# MAGIsCM4Core.net
KiCad netlist of a schematic drawn in Altium Designer
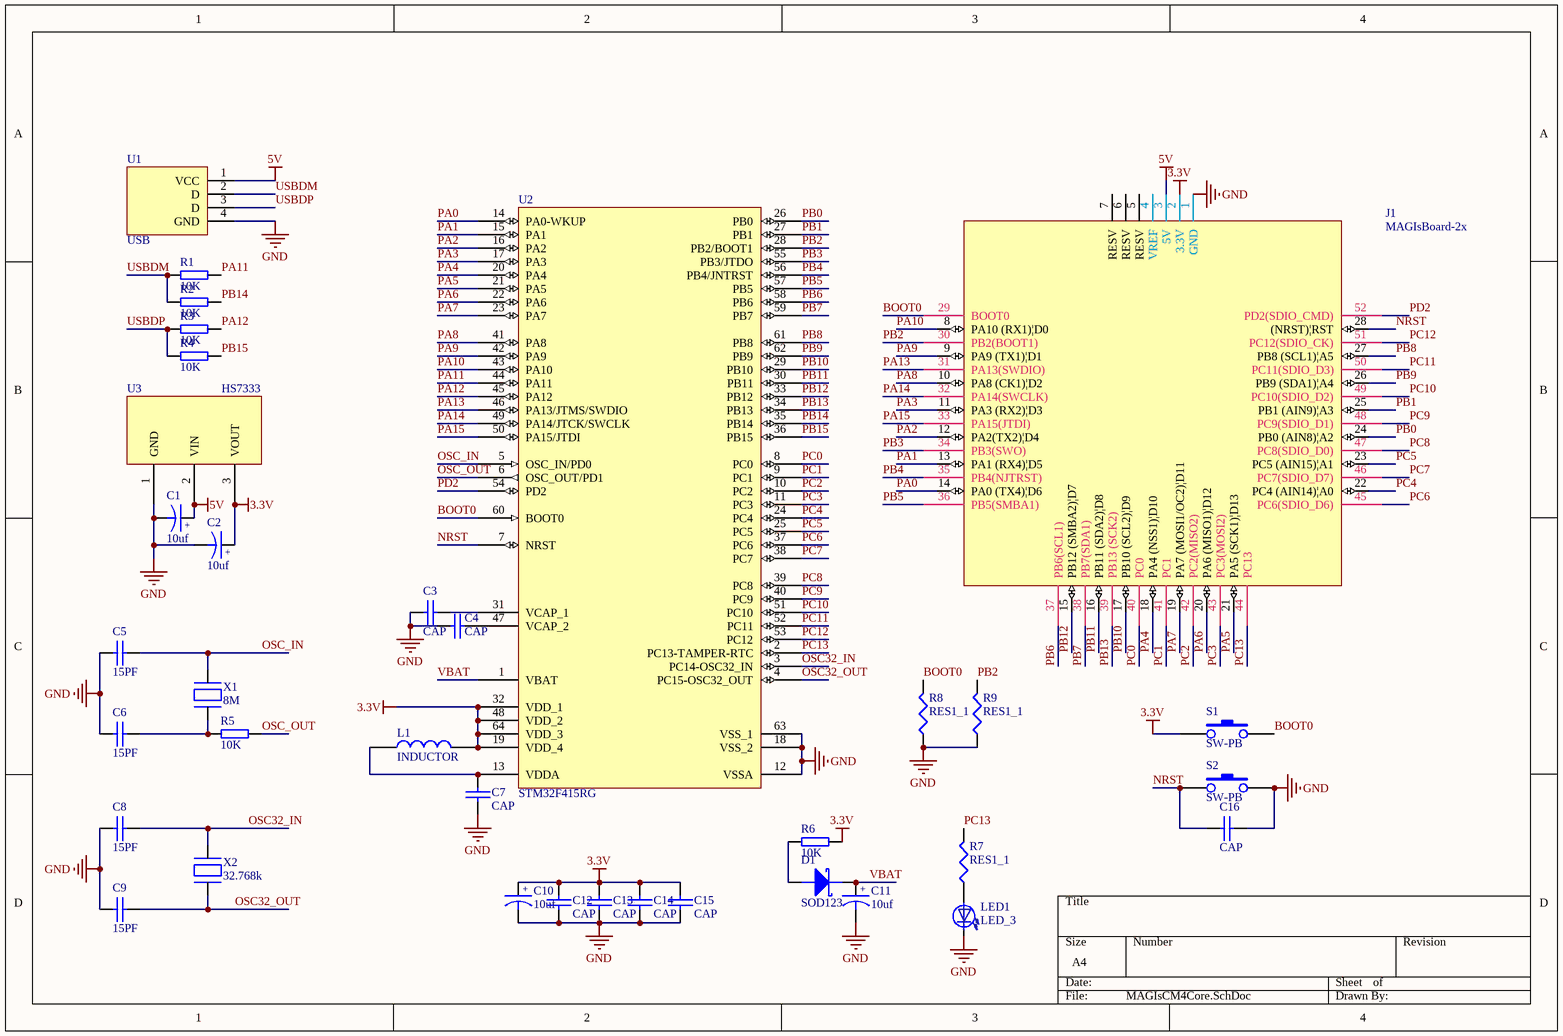
[diagram p0: MAGIsCM4Core.SchDoc]

(export (version "E")
  (design (tool "Eeschema 10.0.6"))
  (components
    (comp (ref "C1")
      (value "10uf")
      (footprint "6-0805_n")
      (description "Capacitor")
      (libsource (lib "电容器") (part "CAPACITOR POL"))
    )
    (comp (ref "C2")
      (value "10uf")
      (footprint "6-0805_n")
      (description "Capacitor")
      (libsource (lib "电容器") (part "CAPACITOR POL"))
    )
    (comp (ref "C3")
      (value "CAP")
      (footprint "6-0805_N")
      (description "Capacitor")
      (libsource (lib "电容器") (part "CAP_1"))
    )
    (comp (ref "C4")
      (value "CAP")
      (footprint "6-0805_N")
      (description "Capacitor")
      (libsource (lib "电容器") (part "CAP_1"))
    )
    (comp (ref "C5") (value "15PF") (footprint "6-0805_n") (libsource (lib "STM32") (part "CAP")))
    (comp (ref "C6") (value "15PF") (footprint "6-0805_n") (libsource (lib "STM32") (part "CAP")))
    (comp (ref "C7")
      (value "CAP")
      (footprint "6-0805_N")
      (description "Capacitor")
      (libsource (lib "电容器") (part "CAP_1"))
    )
    (comp (ref "C8") (value "15PF") (footprint "1608[0603]") (libsource (lib "STM32") (part "CAP")))
    (comp (ref "C9") (value "15PF") (footprint "1608[0603]") (libsource (lib "STM32") (part "CAP")))
    (comp (ref "C10")
      (value "10uf")
      (footprint "C1210_N")
      (description "Capacitor")
      (libsource (lib "电容器") (part "CAPACITOR POL"))
    )
    (comp (ref "C11")
      (value "10uf")
      (footprint "3.3V0.2F-RK")
      (description "Capacitor")
      (libsource (lib "电容器") (part "CAPACITOR POL"))
    )
    (comp (ref "C12")
      (value "CAP")
      (footprint "6-0805_N")
      (description "Capacitor")
      (libsource (lib "电容器") (part "CAP_1"))
    )
    (comp (ref "C13")
      (value "CAP")
      (footprint "6-0805_N")
      (description "Capacitor")
      (libsource (lib "电容器") (part "CAP_1"))
    )
    (comp (ref "C14")
      (value "CAP")
      (footprint "6-0805_N")
      (description "Capacitor")
      (libsource (lib "电容器") (part "CAP_1"))
    )
    (comp (ref "C15")
      (value "CAP")
      (footprint "6-0805_N")
      (description "Capacitor")
      (libsource (lib "电容器") (part "CAP_1"))
    )
    (comp (ref "C16")
      (value "CAP")
      (footprint "6-0805_N")
      (description "Capacitor")
      (libsource (lib "电容器") (part "CAP_1"))
    )
    (comp (ref "D1")
      (value "SOD123")
      (footprint "LL34")
      (description "Schottky Diode")
      (libsource (lib "二极管") (part "DIODE SCHOTTKY_1"))
    )
    (comp (ref "J1")
      (value "MAGIsBoard-2x")
      (footprint "MAGIsBoard-2x")
      (libsource (lib "MAGIsBoard") (part "MAGIsBoard-2x"))
    )
    (comp (ref "L1") (value "INDUCTOR") (footprint "6-0805_n") (libsource (lib "汇总") (part "INDUCTOR")))
    (comp (ref "LED1") (value "LED_3") (footprint "6-0805_N") (libsource (lib "二极管") (part "LED_3")))
    (comp (ref "R1") (value "10K") (footprint "6-0805_n") (libsource (lib "STM32") (part "RES")))
    (comp (ref "R2") (value "10K") (footprint "6-0805_n") (libsource (lib "STM32") (part "RES")))
    (comp (ref "R3") (value "10K") (footprint "6-0805_n") (libsource (lib "STM32") (part "RES")))
    (comp (ref "R4") (value "10K") (footprint "6-0805_n") (libsource (lib "STM32") (part "RES")))
    (comp (ref "R5") (value "10K") (footprint "6-0805_n") (libsource (lib "STM32") (part "RES")))
    (comp (ref "R6") (value "10K") (footprint "6-0805_n") (libsource (lib "STM32") (part "RES")))
    (comp (ref "R7") (value "RES1_1") (footprint "6-0805_N") (libsource (lib "电阻器") (part "RES1_1")))
    (comp (ref "R8") (value "RES1_1") (footprint "6-0805_N") (libsource (lib "电阻器") (part "RES1_1")))
    (comp (ref "R9") (value "RES1_1") (footprint "6-0805_N") (libsource (lib "电阻器") (part "RES1_1")))
    (comp (ref "S1") (value "SW-PB") (footprint "SKRELGE010") (libsource (lib "手动开关") (part "SW-PB")))
    (comp (ref "S2") (value "SW-PB") (footprint "SKRELGE010") (libsource (lib "手动开关") (part "SW-PB")))
    (comp (ref "U1") (value "USB") (footprint "microUSB") (libsource (lib "USB接口") (part "USB")))
    (comp (ref "U2")
      (value "STM32F415RG")
      (footprint "STM32F415RG")
      (libsource (lib "MCU") (part "STM32F415RG"))
    )
    (comp (ref "U3") (value "HS7333") (footprint "HS7333") (libsource (lib "PMIC") (part "HS7333")))
    (comp (ref "X1") (value "8M") (footprint "5032") (libsource (lib "STM32") (part "CRYSTAL")))
    (comp (ref "X2") (value "32.768k") (footprint "3215") (libsource (lib "STM32") (part "CRYSTAL")))
  )
  (nets
    (net (code "1") (name "/BOOT0") (class "Default")
      (node (ref "J1") (pin "29") (pinfunction "BOOT0_29") (pintype "passive"))
      (node (ref "R8") (pin "2") (pinfunction "2_2") (pintype "passive"))
      (node (ref "S1") (pin "2") (pinfunction "2_2") (pintype "passive"))
      (node (ref "U2") (pin "60") (pinfunction "BOOT0_60") (pintype "input"))
    )
    (net (code "2") (name "/NRST") (class "Default")
      (node (ref "C16") (pin "2") (pinfunction "2_2") (pintype "passive"))
      (node (ref "J1") (pin "28") (pinfunction "(NRST)¦RST_28") (pintype "bidirectional"))
      (node (ref "S2") (pin "1") (pinfunction "1_1") (pintype "passive"))
      (node (ref "U2") (pin "7") (pinfunction "NRST_7") (pintype "bidirectional"))
    )
    (net (code "3") (name "/OSC32_IN") (class "Default")
      (node (ref "C8") (pin "2") (pinfunction "2_2") (pintype "passive"))
      (node (ref "U2") (pin "3") (pinfunction "PC14-OSC32_IN_3") (pintype "bidirectional"))
      (node (ref "X2") (pin "1") (pinfunction "1_1") (pintype "passive"))
    )
    (net (code "4") (name "/OSC32_OUT") (class "Default")
      (node (ref "C9") (pin "2") (pinfunction "2_2") (pintype "passive"))
      (node (ref "U2") (pin "4") (pinfunction "PC15-OSC32_OUT_4") (pintype "bidirectional"))
      (node (ref "X2") (pin "2") (pinfunction "2_2") (pintype "passive"))
    )
    (net (code "5") (name "/OSC_IN") (class "Default")
      (node (ref "C5") (pin "2") (pinfunction "2_2") (pintype "passive"))
      (node (ref "U2") (pin "5") (pinfunction "OSC_IN/PD0_5") (pintype "input"))
      (node (ref "X1") (pin "1") (pinfunction "1_1") (pintype "passive"))
    )
    (net (code "6") (name "/OSC_OUT") (class "Default")
      (node (ref "R5") (pin "1") (pinfunction "1_1") (pintype "passive"))
      (node (ref "U2") (pin "6") (pinfunction "OSC_OUT/PD1_6") (pintype "output"))
    )
    (net (code "7") (name "/PA0") (class "Default")
      (node (ref "J1") (pin "14") (pinfunction "PA0_(TX4)¦D6_14") (pintype "bidirectional"))
      (node (ref "U2") (pin "14") (pinfunction "PA0-WKUP_14") (pintype "bidirectional"))
    )
    (net (code "8") (name "/PA1") (class "Default")
      (node (ref "J1") (pin "13") (pinfunction "PA1_(RX4)¦D5_13") (pintype "bidirectional"))
      (node (ref "U2") (pin "15") (pinfunction "PA1_15") (pintype "bidirectional"))
    )
    (net (code "9") (name "/PA2") (class "Default")
      (node (ref "J1") (pin "12") (pinfunction "PA2(TX2)¦D4_12") (pintype "bidirectional"))
      (node (ref "U2") (pin "16") (pinfunction "PA2_16") (pintype "bidirectional"))
    )
    (net (code "10") (name "/PA3") (class "Default")
      (node (ref "J1") (pin "11") (pinfunction "PA3_(RX2)¦D3_11") (pintype "bidirectional"))
      (node (ref "U2") (pin "17") (pinfunction "PA3_17") (pintype "bidirectional"))
    )
    (net (code "11") (name "/PA4") (class "Default")
      (node (ref "J1") (pin "18") (pinfunction "PA4_(NSS1)¦D10_18") (pintype "bidirectional"))
      (node (ref "U2") (pin "20") (pinfunction "PA4_20") (pintype "bidirectional"))
    )
    (net (code "12") (name "/PA5") (class "Default")
      (node (ref "J1") (pin "21") (pinfunction "PA5_(SCK1)¦D13_21") (pintype "bidirectional"))
      (node (ref "U2") (pin "21") (pinfunction "PA5_21") (pintype "bidirectional"))
    )
    (net (code "13") (name "/PA6") (class "Default")
      (node (ref "J1") (pin "20") (pinfunction "PA6_(MISO1)¦D12_20") (pintype "bidirectional"))
      (node (ref "U2") (pin "22") (pinfunction "PA6_22") (pintype "bidirectional"))
    )
    (net (code "14") (name "/PA7") (class "Default")
      (node (ref "J1") (pin "19") (pinfunction "PA7_(MOSI1/OC2)¦D11_19") (pintype "bidirectional"))
      (node (ref "U2") (pin "23") (pinfunction "PA7_23") (pintype "bidirectional"))
    )
    (net (code "15") (name "/PA8") (class "Default")
      (node (ref "J1") (pin "10") (pinfunction "PA8_(CK1)¦D2_10") (pintype "bidirectional"))
      (node (ref "U2") (pin "41") (pinfunction "PA8_41") (pintype "bidirectional"))
    )
    (net (code "16") (name "/PA9") (class "Default")
      (node (ref "J1") (pin "9") (pinfunction "PA9_(TX1)¦D1_9") (pintype "bidirectional"))
      (node (ref "U2") (pin "42") (pinfunction "PA9_42") (pintype "bidirectional"))
    )
    (net (code "17") (name "/PA10") (class "Default")
      (node (ref "J1") (pin "8") (pinfunction "PA10_(RX1)¦D0_8") (pintype "bidirectional"))
      (node (ref "U2") (pin "43") (pinfunction "PA10_43") (pintype "bidirectional"))
    )
    (net (code "18") (name "/PA11") (class "Default")
      (node (ref "R1") (pin "1") (pinfunction "1_1") (pintype "passive"))
      (node (ref "U2") (pin "44") (pinfunction "PA11_44") (pintype "bidirectional"))
    )
    (net (code "19") (name "/PA12") (class "Default")
      (node (ref "R3") (pin "1") (pinfunction "1_1") (pintype "passive"))
      (node (ref "U2") (pin "45") (pinfunction "PA12_45") (pintype "bidirectional"))
    )
    (net (code "20") (name "/PA13") (class "Default")
      (node (ref "J1") (pin "31") (pinfunction "PA13(SWDIO)_31") (pintype "passive"))
      (node (ref "U2") (pin "46") (pinfunction "PA13/JTMS/SWDIO_46") (pintype "bidirectional"))
    )
    (net (code "21") (name "/PA14") (class "Default")
      (node (ref "J1") (pin "32") (pinfunction "PA14(SWCLK)_32") (pintype "passive"))
      (node (ref "U2") (pin "49") (pinfunction "PA14/JTCK/SWCLK_49") (pintype "bidirectional"))
    )
    (net (code "22") (name "/PA15") (class "Default")
      (node (ref "J1") (pin "33") (pinfunction "PA15(JTDI)_33") (pintype "passive"))
      (node (ref "U2") (pin "50") (pinfunction "PA15/JTDI_50") (pintype "bidirectional"))
    )
    (net (code "23") (name "/PB0") (class "Default")
      (node (ref "J1") (pin "24") (pinfunction "PB0_(AIN8)¦A2_24") (pintype "bidirectional"))
      (node (ref "U2") (pin "26") (pinfunction "PB0_26") (pintype "bidirectional"))
    )
    (net (code "24") (name "/PB1") (class "Default")
      (node (ref "J1") (pin "25") (pinfunction "PB1_(AIN9)¦A3_25") (pintype "bidirectional"))
      (node (ref "U2") (pin "27") (pinfunction "PB1_27") (pintype "bidirectional"))
    )
    (net (code "25") (name "/PB2") (class "Default")
      (node (ref "J1") (pin "30") (pinfunction "PB2(BOOT1)_30") (pintype "passive"))
      (node (ref "R9") (pin "2") (pinfunction "2_2") (pintype "passive"))
      (node (ref "U2") (pin "28") (pinfunction "PB2/BOOT1_28") (pintype "bidirectional"))
    )
    (net (code "26") (name "/PB3") (class "Default")
      (node (ref "J1") (pin "34") (pinfunction "PB3(SWO)_34") (pintype "passive"))
      (node (ref "U2") (pin "55") (pinfunction "PB3/JTDO_55") (pintype "bidirectional"))
    )
    (net (code "27") (name "/PB4") (class "Default")
      (node (ref "J1") (pin "35") (pinfunction "PB4(NJTRST)_35") (pintype "passive"))
      (node (ref "U2") (pin "56") (pinfunction "PB4/JNTRST_56") (pintype "bidirectional"))
    )
    (net (code "28") (name "/PB5") (class "Default")
      (node (ref "J1") (pin "36") (pinfunction "PB5(SMBA1)_36") (pintype "passive"))
      (node (ref "U2") (pin "57") (pinfunction "PB5_57") (pintype "bidirectional"))
    )
    (net (code "29") (name "/PB6") (class "Default")
      (node (ref "J1") (pin "37") (pinfunction "PB6(SCL1)_37") (pintype "passive"))
      (node (ref "U2") (pin "58") (pinfunction "PB6_58") (pintype "bidirectional"))
    )
    (net (code "30") (name "/PB7") (class "Default")
      (node (ref "J1") (pin "38") (pinfunction "PB7(SDA1)_38") (pintype "passive"))
      (node (ref "U2") (pin "59") (pinfunction "PB7_59") (pintype "bidirectional"))
    )
    (net (code "31") (name "/PB8") (class "Default")
      (node (ref "J1") (pin "27") (pinfunction "PB8_(SCL1)¦A5_27") (pintype "bidirectional"))
      (node (ref "U2") (pin "61") (pinfunction "PB8_61") (pintype "bidirectional"))
    )
    (net (code "32") (name "/PB9") (class "Default")
      (node (ref "J1") (pin "26") (pinfunction "PB9_(SDA1)¦A4_26") (pintype "bidirectional"))
      (node (ref "U2") (pin "62") (pinfunction "PB9_62") (pintype "bidirectional"))
    )
    (net (code "33") (name "/PB10") (class "Default")
      (node (ref "J1") (pin "17") (pinfunction "PB10_(SCL2)¦D9_17") (pintype "bidirectional"))
      (node (ref "U2") (pin "29") (pinfunction "PB10_29") (pintype "bidirectional"))
    )
    (net (code "34") (name "/PB11") (class "Default")
      (node (ref "J1") (pin "16") (pinfunction "PB11_(SDA2)¦D8_16") (pintype "bidirectional"))
      (node (ref "U2") (pin "30") (pinfunction "PB11_30") (pintype "bidirectional"))
    )
    (net (code "35") (name "/PB12") (class "Default")
      (node (ref "J1") (pin "15") (pinfunction "PB12_(SMBA2)¦D7_15") (pintype "bidirectional"))
      (node (ref "U2") (pin "33") (pinfunction "PB12_33") (pintype "bidirectional"))
    )
    (net (code "36") (name "/PB13") (class "Default")
      (node (ref "J1") (pin "39") (pinfunction "PB13_(SCK2)_39") (pintype "passive"))
      (node (ref "U2") (pin "34") (pinfunction "PB13_34") (pintype "bidirectional"))
    )
    (net (code "37") (name "/PB14") (class "Default")
      (node (ref "R2") (pin "1") (pinfunction "1_1") (pintype "passive"))
      (node (ref "U2") (pin "35") (pinfunction "PB14_35") (pintype "bidirectional"))
    )
    (net (code "38") (name "/PB15") (class "Default")
      (node (ref "R4") (pin "1") (pinfunction "1_1") (pintype "passive"))
      (node (ref "U2") (pin "36") (pinfunction "PB15_36") (pintype "bidirectional"))
    )
    (net (code "39") (name "/PC0") (class "Default")
      (node (ref "J1") (pin "40") (pinfunction "PC0_40") (pintype "passive"))
      (node (ref "U2") (pin "8") (pinfunction "PC0_8") (pintype "bidirectional"))
    )
    (net (code "40") (name "/PC1") (class "Default")
      (node (ref "J1") (pin "41") (pinfunction "PC1_41") (pintype "passive"))
      (node (ref "U2") (pin "9") (pinfunction "PC1_9") (pintype "bidirectional"))
    )
    (net (code "41") (name "/PC2") (class "Default")
      (node (ref "J1") (pin "42") (pinfunction "PC2(MISO2)_42") (pintype "passive"))
      (node (ref "U2") (pin "10") (pinfunction "PC2_10") (pintype "bidirectional"))
    )
    (net (code "42") (name "/PC3") (class "Default")
      (node (ref "J1") (pin "43") (pinfunction "PC3(MOSI2)_43") (pintype "passive"))
      (node (ref "U2") (pin "11") (pinfunction "PC3_11") (pintype "bidirectional"))
    )
    (net (code "43") (name "/PC4") (class "Default")
      (node (ref "J1") (pin "22") (pinfunction "PC4_(AIN14)¦A0_22") (pintype "bidirectional"))
      (node (ref "U2") (pin "24") (pinfunction "PC4_24") (pintype "bidirectional"))
    )
    (net (code "44") (name "/PC5") (class "Default")
      (node (ref "J1") (pin "23") (pinfunction "PC5_(AIN15)¦A1_23") (pintype "bidirectional"))
      (node (ref "U2") (pin "25") (pinfunction "PC5_25") (pintype "bidirectional"))
    )
    (net (code "45") (name "/PC6") (class "Default")
      (node (ref "J1") (pin "45") (pinfunction "PC6(SDIO_D6)_45") (pintype "passive"))
      (node (ref "U2") (pin "37") (pinfunction "PC6_37") (pintype "bidirectional"))
    )
    (net (code "46") (name "/PC7") (class "Default")
      (node (ref "J1") (pin "46") (pinfunction "PC7(SDIO_D7)_46") (pintype "passive"))
      (node (ref "U2") (pin "38") (pinfunction "PC7_38") (pintype "bidirectional"))
    )
    (net (code "47") (name "/PC8") (class "Default")
      (node (ref "J1") (pin "47") (pinfunction "PC8(SDIO_D0)_47") (pintype "passive"))
      (node (ref "U2") (pin "39") (pinfunction "PC8_39") (pintype "bidirectional"))
    )
    (net (code "48") (name "/PC9") (class "Default")
      (node (ref "J1") (pin "48") (pinfunction "PC9(SDIO_D1)_48") (pintype "passive"))
      (node (ref "U2") (pin "40") (pinfunction "PC9_40") (pintype "bidirectional"))
    )
    (net (code "49") (name "/PC10") (class "Default")
      (node (ref "J1") (pin "49") (pinfunction "PC10(SDIO_D2)_49") (pintype "passive"))
      (node (ref "U2") (pin "51") (pinfunction "PC10_51") (pintype "bidirectional"))
    )
    (net (code "50") (name "/PC11") (class "Default")
      (node (ref "J1") (pin "50") (pinfunction "PC11(SDIO_D3)_50") (pintype "passive"))
      (node (ref "U2") (pin "52") (pinfunction "PC11_52") (pintype "bidirectional"))
    )
    (net (code "51") (name "/PC12") (class "Default")
      (node (ref "J1") (pin "51") (pinfunction "PC12(SDIO_CK)_51") (pintype "passive"))
      (node (ref "U2") (pin "53") (pinfunction "PC12_53") (pintype "bidirectional"))
    )
    (net (code "52") (name "/PC13") (class "Default")
      (node (ref "J1") (pin "44") (pinfunction "PC13_44") (pintype "passive"))
      (node (ref "R7") (pin "2") (pinfunction "2_2") (pintype "passive"))
      (node (ref "U2") (pin "2") (pinfunction "PC13-TAMPER-RTC_2") (pintype "bidirectional"))
    )
    (net (code "53") (name "/PD2") (class "Default")
      (node (ref "J1") (pin "52") (pinfunction "PD2(SDIO_CMD)_52") (pintype "passive"))
      (node (ref "U2") (pin "54") (pinfunction "PD2_54") (pintype "bidirectional"))
    )
    (net (code "54") (name "/USBDM") (class "Default")
      (node (ref "R1") (pin "2") (pinfunction "2_2") (pintype "passive"))
      (node (ref "R2") (pin "2") (pinfunction "2_2") (pintype "passive"))
      (node (ref "U1") (pin "2") (pinfunction "D_2") (pintype "passive"))
    )
    (net (code "55") (name "/USBDP") (class "Default")
      (node (ref "R3") (pin "2") (pinfunction "2_2") (pintype "passive"))
      (node (ref "R4") (pin "2") (pinfunction "2_2") (pintype "passive"))
      (node (ref "U1") (pin "3") (pinfunction "D_3") (pintype "passive"))
    )
    (net (code "56") (name "/VBAT") (class "Default")
      (node (ref "C11") (pin "1") (pinfunction "1_1") (pintype "passive"))
      (node (ref "D1") (pin "2") (pinfunction "K_2") (pintype "passive"))
      (node (ref "U2") (pin "1") (pinfunction "VBAT_1") (pintype "power_in"))
    )
    (net (code "57") (name "3.3V") (class "Default")
      (node (ref "C10") (pin "1") (pinfunction "1_1") (pintype "passive"))
      (node (ref "C12") (pin "2") (pinfunction "2_2") (pintype "passive"))
      (node (ref "C13") (pin "2") (pinfunction "2_2") (pintype "passive"))
      (node (ref "C14") (pin "2") (pinfunction "2_2") (pintype "passive"))
      (node (ref "C15") (pin "2") (pinfunction "2_2") (pintype "passive"))
      (node (ref "C2") (pin "1") (pinfunction "1_1") (pintype "passive"))
      (node (ref "J1") (pin "2") (pinfunction "3.3V_2") (pintype "power_in"))
      (node (ref "L1") (pin "2") (pinfunction "2_2") (pintype "passive"))
      (node (ref "R6") (pin "1") (pinfunction "1_1") (pintype "passive"))
      (node (ref "S1") (pin "1") (pinfunction "1_1") (pintype "passive"))
      (node (ref "U2") (pin "19") (pinfunction "VDD_4_19") (pintype "power_in"))
      (node (ref "U2") (pin "32") (pinfunction "VDD_1_32") (pintype "power_in"))
      (node (ref "U2") (pin "48") (pinfunction "VDD_2_48") (pintype "power_in"))
      (node (ref "U2") (pin "64") (pinfunction "VDD_3_64") (pintype "power_in"))
      (node (ref "U3") (pin "3") (pinfunction "VOUT_3") (pintype "passive"))
    )
    (net (code "58") (name "5V") (class "Default")
      (node (ref "C1") (pin "1") (pinfunction "1_1") (pintype "passive"))
      (node (ref "J1") (pin "3") (pinfunction "5V_3") (pintype "power_in"))
      (node (ref "U1") (pin "1") (pinfunction "VCC_1") (pintype "passive"))
      (node (ref "U3") (pin "2") (pinfunction "VIN_2") (pintype "passive"))
    )
    (net (code "59") (name "GND") (class "Default")
      (node (ref "C1") (pin "2") (pinfunction "2_2") (pintype "passive"))
      (node (ref "C10") (pin "2") (pinfunction "2_2") (pintype "passive"))
      (node (ref "C11") (pin "2") (pinfunction "2_2") (pintype "passive"))
      (node (ref "C12") (pin "1") (pinfunction "1_1") (pintype "passive"))
      (node (ref "C13") (pin "1") (pinfunction "1_1") (pintype "passive"))
      (node (ref "C14") (pin "1") (pinfunction "1_1") (pintype "passive"))
      (node (ref "C15") (pin "1") (pinfunction "1_1") (pintype "passive"))
      (node (ref "C16") (pin "1") (pinfunction "1_1") (pintype "passive"))
      (node (ref "C2") (pin "2") (pinfunction "2_2") (pintype "passive"))
      (node (ref "C3") (pin "1") (pinfunction "1_1") (pintype "passive"))
      (node (ref "C4") (pin "1") (pinfunction "1_1") (pintype "passive"))
      (node (ref "C5") (pin "1") (pinfunction "1_1") (pintype "passive"))
      (node (ref "C6") (pin "1") (pinfunction "1_1") (pintype "passive"))
      (node (ref "C7") (pin "2") (pinfunction "2_2") (pintype "passive"))
      (node (ref "C8") (pin "1") (pinfunction "1_1") (pintype "passive"))
      (node (ref "C9") (pin "1") (pinfunction "1_1") (pintype "passive"))
      (node (ref "J1") (pin "1") (pinfunction "GND_1") (pintype "power_in"))
      (node (ref "LED1") (pin "2") (pinfunction "K_2") (pintype "passive"))
      (node (ref "R8") (pin "1") (pinfunction "1_1") (pintype "passive"))
      (node (ref "R9") (pin "1") (pinfunction "1_1") (pintype "passive"))
      (node (ref "S2") (pin "2") (pinfunction "2_2") (pintype "passive"))
      (node (ref "U1") (pin "4") (pinfunction "GND_4") (pintype "passive"))
      (node (ref "U2") (pin "12") (pinfunction "VSSA_12") (pintype "power_in"))
      (node (ref "U2") (pin "18") (pinfunction "VSS_2_18") (pintype "power_in"))
      (node (ref "U2") (pin "63") (pinfunction "VSS_1_63") (pintype "power_in"))
      (node (ref "U3") (pin "1") (pinfunction "GND_1") (pintype "passive"))
    )
    (net (code "60") (name "Net-(C6-Pad2)") (class "Default")
      (node (ref "C6") (pin "2") (pinfunction "2_2") (pintype "passive"))
      (node (ref "R5") (pin "2") (pinfunction "2_2") (pintype "passive"))
      (node (ref "X1") (pin "2") (pinfunction "2_2") (pintype "passive"))
    )
    (net (code "61") (name "Net-(D1-A)") (class "Default")
      (node (ref "D1") (pin "1") (pinfunction "A_1") (pintype "passive"))
      (node (ref "R6") (pin "2") (pinfunction "2_2") (pintype "passive"))
    )
    (net (code "62") (name "Net-(LED1-A)") (class "Default")
      (node (ref "LED1") (pin "1") (pinfunction "A_1") (pintype "passive"))
      (node (ref "R7") (pin "1") (pinfunction "1_1") (pintype "passive"))
    )
    (net (code "63") (name "Net-(U2-VCAP_1)") (class "Default")
      (node (ref "C3") (pin "2") (pinfunction "2_2") (pintype "passive"))
      (node (ref "U2") (pin "31") (pinfunction "VCAP_1_31") (pintype "power_in"))
    )
    (net (code "64") (name "Net-(U2-VCAP_2)") (class "Default")
      (node (ref "C4") (pin "2") (pinfunction "2_2") (pintype "passive"))
      (node (ref "U2") (pin "47") (pinfunction "VCAP_2_47") (pintype "power_in"))
    )
    (net (code "65") (name "Net-(U2-VDDA)") (class "Default")
      (node (ref "C7") (pin "1") (pinfunction "1_1") (pintype "passive"))
      (node (ref "L1") (pin "1") (pinfunction "1_1") (pintype "passive"))
      (node (ref "U2") (pin "13") (pinfunction "VDDA_13") (pintype "power_in"))
    )
    (net (code "66") (name "unconnected-(J1-RESV-Pad5)") (class "Default")
      (node (ref "J1") (pin "5") (pinfunction "RESV_5") (pintype "passive"))
    )
    (net (code "67") (name "unconnected-(J1-RESV-Pad6)") (class "Default")
      (node (ref "J1") (pin "6") (pinfunction "RESV_6") (pintype "passive"))
    )
    (net (code "68") (name "unconnected-(J1-RESV-Pad7)") (class "Default")
      (node (ref "J1") (pin "7") (pinfunction "RESV_7") (pintype "passive"))
    )
    (net (code "69") (name "unconnected-(J1-VREF-Pad4)") (class "Default")
      (node (ref "J1") (pin "4") (pinfunction "VREF_4") (pintype "passive"))
    )
  )
)
